# Orgel.net
KiCad netlist of a schematic drawn in EAGLE
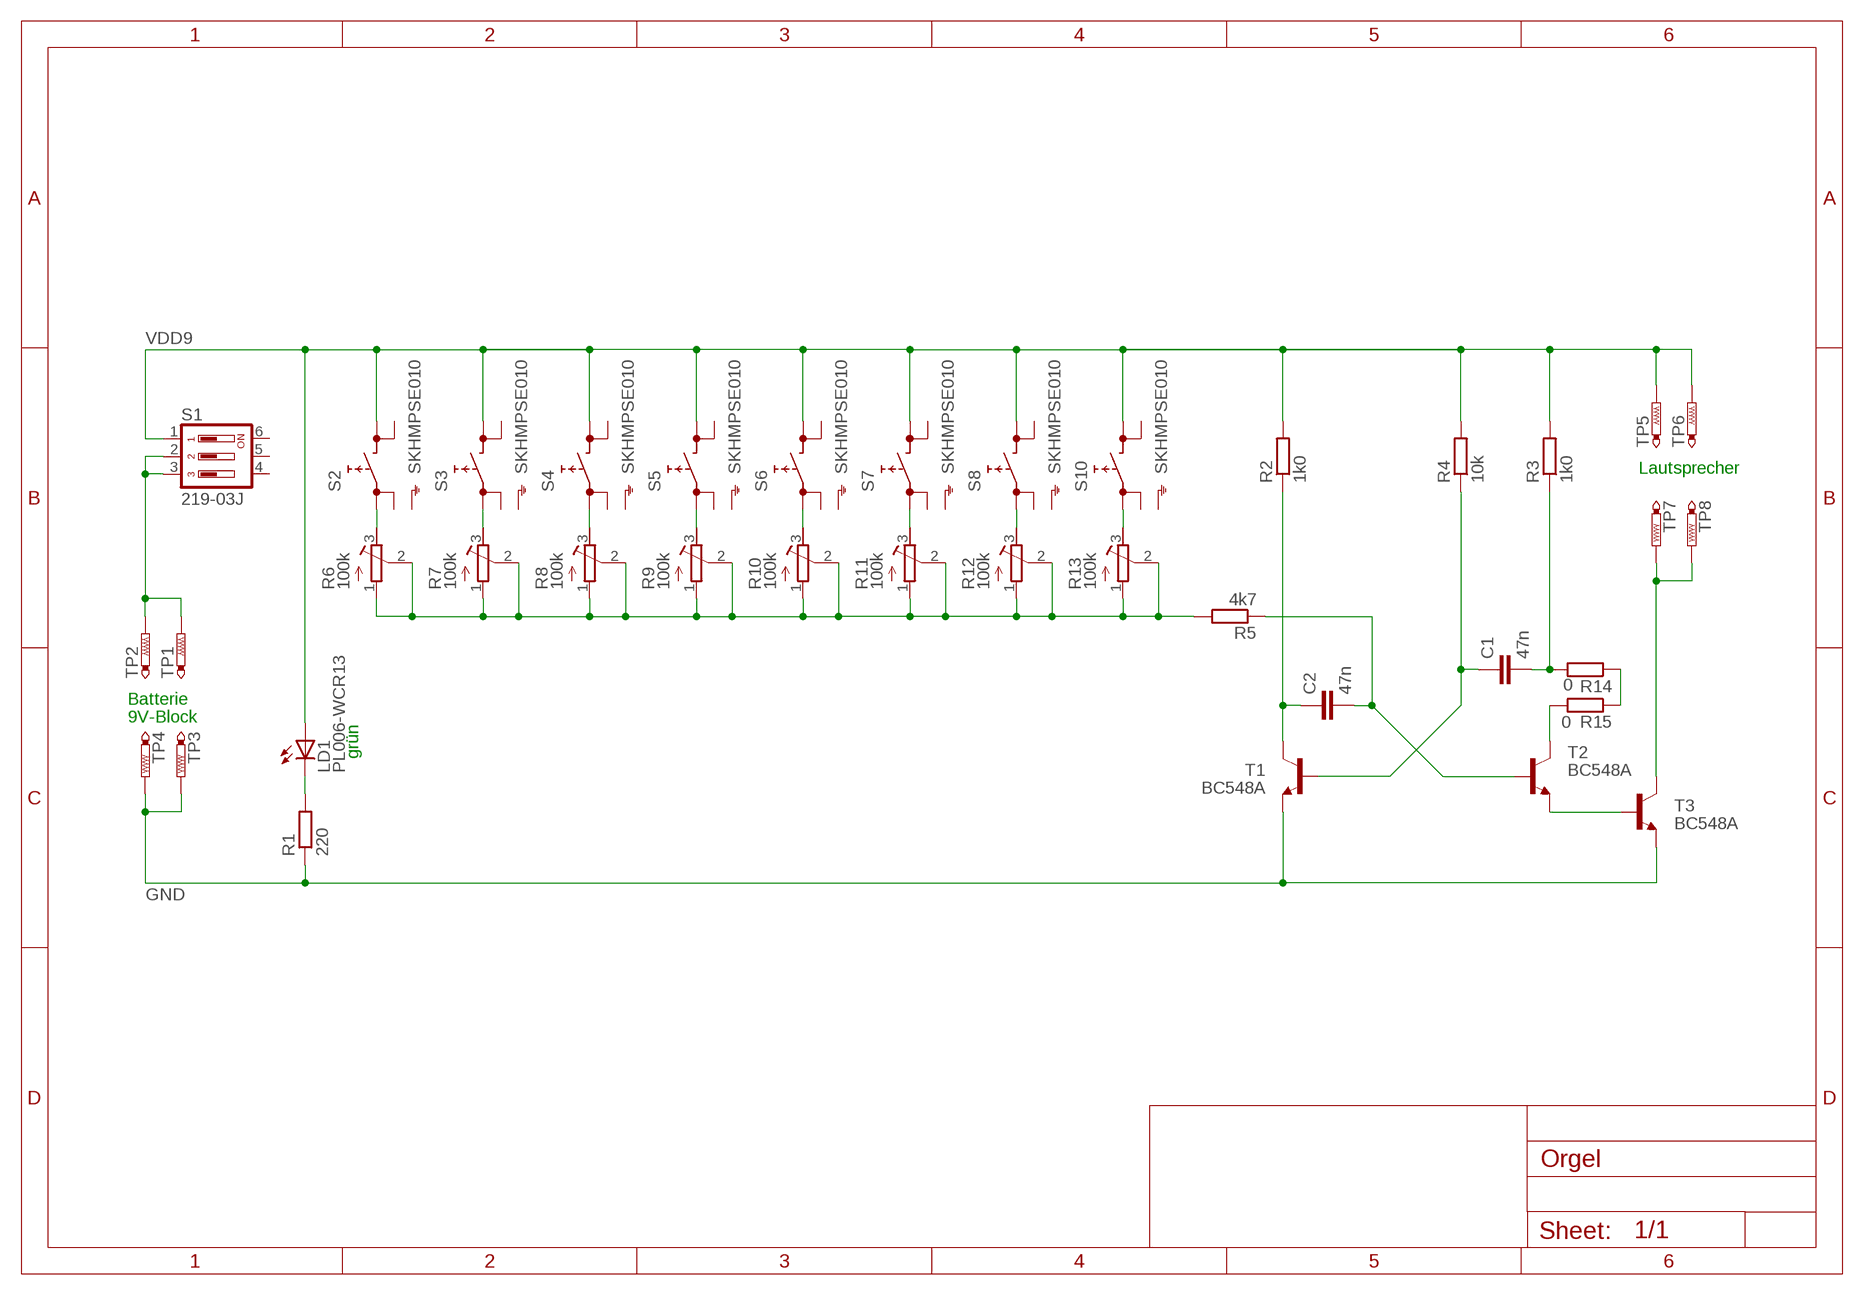
[diagram p0: schematic, sheet 1]

(export (version "E")
  (design (tool "Eeschema 10.0.6"))
  (components
    (comp (ref "C1")
      (value "47n")
      (footprint "eagle-import:C1206")
      (libsource (lib "eagle-import") (part "C-EUC1206"))
    )
    (comp (ref "C2")
      (value "47n")
      (footprint "eagle-import:C1206")
      (libsource (lib "eagle-import") (part "C-EUC1206"))
    )
    (comp (ref "LD1")
      (value "PL006-WCR13")
      (footprint "eagle-import:SOT23")
      (libsource (lib "eagle-import") (part "PL006-WCR13"))
    )
    (comp (ref "R1")
      (value "220")
      (footprint "eagle-import:M1206")
      (libsource (lib "eagle-import") (part "R-EU_M1206"))
    )
    (comp (ref "R2")
      (value "1k0")
      (footprint "eagle-import:M1206")
      (libsource (lib "eagle-import") (part "R-EU_M1206"))
    )
    (comp (ref "R3")
      (value "1k0")
      (footprint "eagle-import:M1206")
      (libsource (lib "eagle-import") (part "R-EU_M1206"))
    )
    (comp (ref "R4")
      (value "10k")
      (footprint "eagle-import:M1206")
      (libsource (lib "eagle-import") (part "R-EU_M1206"))
    )
    (comp (ref "R5")
      (value "4k7")
      (footprint "eagle-import:M1206")
      (libsource (lib "eagle-import") (part "R-EU_M1206"))
    )
    (comp (ref "R6")
      (value "100k")
      (footprint "eagle-import:RTRIM5X")
      (libsource (lib "eagle-import") (part "R-TRIMM5X"))
    )
    (comp (ref "R7")
      (value "100k")
      (footprint "eagle-import:RTRIM5X")
      (libsource (lib "eagle-import") (part "R-TRIMM5X"))
    )
    (comp (ref "R8")
      (value "100k")
      (footprint "eagle-import:RTRIM5X")
      (libsource (lib "eagle-import") (part "R-TRIMM5X"))
    )
    (comp (ref "R9")
      (value "100k")
      (footprint "eagle-import:RTRIM5X")
      (libsource (lib "eagle-import") (part "R-TRIMM5X"))
    )
    (comp (ref "R10")
      (value "100k")
      (footprint "eagle-import:RTRIM5X")
      (libsource (lib "eagle-import") (part "R-TRIMM5X"))
    )
    (comp (ref "R11")
      (value "100k")
      (footprint "eagle-import:RTRIM5X")
      (libsource (lib "eagle-import") (part "R-TRIMM5X"))
    )
    (comp (ref "R12")
      (value "100k")
      (footprint "eagle-import:RTRIM5X")
      (libsource (lib "eagle-import") (part "R-TRIMM5X"))
    )
    (comp (ref "R13")
      (value "100k")
      (footprint "eagle-import:RTRIM5X")
      (libsource (lib "eagle-import") (part "R-TRIMM5X"))
    )
    (comp (ref "R14")
      (value "0")
      (footprint "eagle-import:M5923")
      (libsource (lib "eagle-import") (part "R-EU_M5923"))
    )
    (comp (ref "R15")
      (value "0")
      (footprint "eagle-import:M5923")
      (libsource (lib "eagle-import") (part "R-EU_M5923"))
    )
    (comp (ref "S1")
      (value "219-03J")
      (footprint "eagle-import:CTS-219-03J")
      (libsource (lib "eagle-import") (part "219-03J"))
    )
    (comp (ref "S2")
      (value "SKHMPSE010")
      (footprint "eagle-import:SKHMPXE010")
      (libsource (lib "eagle-import") (part "SKHMPE010S"))
    )
    (comp (ref "S3")
      (value "SKHMPSE010")
      (footprint "eagle-import:SKHMPXE010")
      (libsource (lib "eagle-import") (part "SKHMPE010S"))
    )
    (comp (ref "S4")
      (value "SKHMPSE010")
      (footprint "eagle-import:SKHMPXE010")
      (libsource (lib "eagle-import") (part "SKHMPE010S"))
    )
    (comp (ref "S5")
      (value "SKHMPSE010")
      (footprint "eagle-import:SKHMPXE010")
      (libsource (lib "eagle-import") (part "SKHMPE010S"))
    )
    (comp (ref "S6")
      (value "SKHMPSE010")
      (footprint "eagle-import:SKHMPXE010")
      (libsource (lib "eagle-import") (part "SKHMPE010S"))
    )
    (comp (ref "S7")
      (value "SKHMPSE010")
      (footprint "eagle-import:SKHMPXE010")
      (libsource (lib "eagle-import") (part "SKHMPE010S"))
    )
    (comp (ref "S8")
      (value "SKHMPSE010")
      (footprint "eagle-import:SKHMPXE010")
      (libsource (lib "eagle-import") (part "SKHMPE010S"))
    )
    (comp (ref "S10")
      (value "SKHMPSE010")
      (footprint "eagle-import:SKHMPXE010")
      (libsource (lib "eagle-import") (part "SKHMPE010S"))
    )
    (comp (ref "T1")
      (value "BC548A")
      (footprint "eagle-import:SOT23-EBC")
      (libsource (lib "eagle-import") (part "-NPN-SOT23-EBC"))
    )
    (comp (ref "T2")
      (value "BC548A")
      (footprint "eagle-import:SOT23-EBC")
      (libsource (lib "eagle-import") (part "-NPN-SOT23-EBC"))
    )
    (comp (ref "T3")
      (value "BC548A")
      (footprint "eagle-import:SOT23-EBC")
      (libsource (lib "eagle-import") (part "-NPN-SOT23-EBC"))
    )
    (comp (ref "TP1")
      (value "PTR1TP20SQ")
      (footprint "eagle-import:TP20SQ")
      (libsource (lib "eagle-import") (part "PTR1TP20SQ"))
    )
    (comp (ref "TP2")
      (value "PTR1TP20SQ")
      (footprint "eagle-import:TP20SQ")
      (libsource (lib "eagle-import") (part "PTR1TP20SQ"))
    )
    (comp (ref "TP3")
      (value "PTR1TP20SQ")
      (footprint "eagle-import:TP20SQ")
      (libsource (lib "eagle-import") (part "PTR1TP20SQ"))
    )
    (comp (ref "TP4")
      (value "PTR1TP20SQ")
      (footprint "eagle-import:TP20SQ")
      (libsource (lib "eagle-import") (part "PTR1TP20SQ"))
    )
    (comp (ref "TP5")
      (value "PTR1TP20SQ")
      (footprint "eagle-import:TP20SQ")
      (libsource (lib "eagle-import") (part "PTR1TP20SQ"))
    )
    (comp (ref "TP6")
      (value "PTR1TP20SQ")
      (footprint "eagle-import:TP20SQ")
      (libsource (lib "eagle-import") (part "PTR1TP20SQ"))
    )
    (comp (ref "TP7")
      (value "PTR1TP20SQ")
      (footprint "eagle-import:TP20SQ")
      (libsource (lib "eagle-import") (part "PTR1TP20SQ"))
    )
    (comp (ref "TP8")
      (value "PTR1TP20SQ")
      (footprint "eagle-import:TP20SQ")
      (libsource (lib "eagle-import") (part "PTR1TP20SQ"))
    )
  )
  (nets
    (net (code "1") (name "/GND") (class "Default")
      (node (ref "R1") (pin "1") (pinfunction "1_1") (pintype "passive"))
      (node (ref "T1") (pin "E") (pinfunction "E_E") (pintype "passive"))
      (node (ref "T3") (pin "E") (pinfunction "E_E") (pintype "passive"))
      (node (ref "TP3") (pin "TP") (pinfunction "TP_TP") (pintype "input"))
      (node (ref "TP4") (pin "TP") (pinfunction "TP_TP") (pintype "input"))
    )
    (net (code "2") (name "/VDD9") (class "Default")
      (node (ref "LD1") (pin "1") (pinfunction "A_1") (pintype "passive"))
      (node (ref "R2") (pin "2") (pinfunction "2_2") (pintype "passive"))
      (node (ref "R3") (pin "2") (pinfunction "2_2") (pintype "passive"))
      (node (ref "R4") (pin "2") (pinfunction "2_2") (pintype "passive"))
      (node (ref "S1") (pin "1") (pinfunction "1_1") (pintype "passive"))
      (node (ref "S10") (pin "3") (pinfunction "2.1_3") (pintype "passive"))
      (node (ref "S2") (pin "3") (pinfunction "2.1_3") (pintype "passive"))
      (node (ref "S3") (pin "3") (pinfunction "2.1_3") (pintype "passive"))
      (node (ref "S4") (pin "3") (pinfunction "2.1_3") (pintype "passive"))
      (node (ref "S5") (pin "3") (pinfunction "2.1_3") (pintype "passive"))
      (node (ref "S6") (pin "3") (pinfunction "2.1_3") (pintype "passive"))
      (node (ref "S7") (pin "3") (pinfunction "2.1_3") (pintype "passive"))
      (node (ref "S8") (pin "3") (pinfunction "2.1_3") (pintype "passive"))
      (node (ref "TP5") (pin "TP") (pinfunction "TP_TP") (pintype "input"))
      (node (ref "TP6") (pin "TP") (pinfunction "TP_TP") (pintype "input"))
    )
    (net (code "3") (name "Net-(C1-Pad1)") (class "Default")
      (node (ref "C1") (pin "1") (pinfunction "1_1") (pintype "passive"))
      (node (ref "R4") (pin "1") (pinfunction "1_1") (pintype "passive"))
      (node (ref "T1") (pin "B") (pinfunction "B_B") (pintype "passive"))
    )
    (net (code "4") (name "Net-(C1-Pad2)") (class "Default")
      (node (ref "C1") (pin "2") (pinfunction "2_2") (pintype "passive"))
      (node (ref "R14") (pin "2") (pinfunction "2_2") (pintype "passive"))
      (node (ref "R3") (pin "1") (pinfunction "1_1") (pintype "passive"))
    )
    (net (code "5") (name "Net-(C2-Pad1)") (class "Default")
      (node (ref "C2") (pin "1") (pinfunction "1_1") (pintype "passive"))
      (node (ref "R2") (pin "1") (pinfunction "1_1") (pintype "passive"))
      (node (ref "T1") (pin "C") (pinfunction "C_C") (pintype "passive"))
    )
    (net (code "6") (name "Net-(C2-Pad2)") (class "Default")
      (node (ref "C2") (pin "2") (pinfunction "2_2") (pintype "passive"))
      (node (ref "R5") (pin "1") (pinfunction "1_1") (pintype "passive"))
      (node (ref "T2") (pin "B") (pinfunction "B_B") (pintype "passive"))
    )
    (net (code "7") (name "Net-(LD1-C)") (class "Default")
      (node (ref "LD1") (pin "3") (pinfunction "C_3") (pintype "passive"))
      (node (ref "R1") (pin "2") (pinfunction "2_2") (pintype "passive"))
    )
    (net (code "8") (name "Net-(R6-E)") (class "Default")
      (node (ref "R6") (pin "3") (pinfunction "E_3") (pintype "passive"))
      (node (ref "S2") (pin "1") (pinfunction "1.1_1") (pintype "passive"))
    )
    (net (code "9") (name "Net-(R7-E)") (class "Default")
      (node (ref "R7") (pin "3") (pinfunction "E_3") (pintype "passive"))
      (node (ref "S3") (pin "1") (pinfunction "1.1_1") (pintype "passive"))
    )
    (net (code "10") (name "Net-(R8-E)") (class "Default")
      (node (ref "R8") (pin "3") (pinfunction "E_3") (pintype "passive"))
      (node (ref "S4") (pin "1") (pinfunction "1.1_1") (pintype "passive"))
    )
    (net (code "11") (name "Net-(R9-E)") (class "Default")
      (node (ref "R9") (pin "3") (pinfunction "E_3") (pintype "passive"))
      (node (ref "S5") (pin "1") (pinfunction "1.1_1") (pintype "passive"))
    )
    (net (code "12") (name "Net-(R10-A)") (class "Default")
      (node (ref "R10") (pin "1") (pinfunction "A_1") (pintype "passive"))
      (node (ref "R10") (pin "2") (pinfunction "S_2") (pintype "passive"))
      (node (ref "R11") (pin "1") (pinfunction "A_1") (pintype "passive"))
      (node (ref "R11") (pin "2") (pinfunction "S_2") (pintype "passive"))
      (node (ref "R12") (pin "1") (pinfunction "A_1") (pintype "passive"))
      (node (ref "R12") (pin "2") (pinfunction "S_2") (pintype "passive"))
      (node (ref "R13") (pin "1") (pinfunction "A_1") (pintype "passive"))
      (node (ref "R13") (pin "2") (pinfunction "S_2") (pintype "passive"))
      (node (ref "R5") (pin "2") (pinfunction "2_2") (pintype "passive"))
      (node (ref "R6") (pin "1") (pinfunction "A_1") (pintype "passive"))
      (node (ref "R6") (pin "2") (pinfunction "S_2") (pintype "passive"))
      (node (ref "R7") (pin "1") (pinfunction "A_1") (pintype "passive"))
      (node (ref "R7") (pin "2") (pinfunction "S_2") (pintype "passive"))
      (node (ref "R8") (pin "1") (pinfunction "A_1") (pintype "passive"))
      (node (ref "R8") (pin "2") (pinfunction "S_2") (pintype "passive"))
      (node (ref "R9") (pin "1") (pinfunction "A_1") (pintype "passive"))
      (node (ref "R9") (pin "2") (pinfunction "S_2") (pintype "passive"))
    )
    (net (code "13") (name "Net-(R10-E)") (class "Default")
      (node (ref "R10") (pin "3") (pinfunction "E_3") (pintype "passive"))
      (node (ref "S6") (pin "1") (pinfunction "1.1_1") (pintype "passive"))
    )
    (net (code "14") (name "Net-(R11-E)") (class "Default")
      (node (ref "R11") (pin "3") (pinfunction "E_3") (pintype "passive"))
      (node (ref "S7") (pin "1") (pinfunction "1.1_1") (pintype "passive"))
    )
    (net (code "15") (name "Net-(R12-E)") (class "Default")
      (node (ref "R12") (pin "3") (pinfunction "E_3") (pintype "passive"))
      (node (ref "S8") (pin "1") (pinfunction "1.1_1") (pintype "passive"))
    )
    (net (code "16") (name "Net-(R13-E)") (class "Default")
      (node (ref "R13") (pin "3") (pinfunction "E_3") (pintype "passive"))
      (node (ref "S10") (pin "1") (pinfunction "1.1_1") (pintype "passive"))
    )
    (net (code "17") (name "Net-(R14-Pad1)") (class "Default")
      (node (ref "R14") (pin "1") (pinfunction "1_1") (pintype "passive"))
      (node (ref "R15") (pin "1") (pinfunction "1_1") (pintype "passive"))
    )
    (net (code "18") (name "Net-(R15-Pad2)") (class "Default")
      (node (ref "R15") (pin "2") (pinfunction "2_2") (pintype "passive"))
      (node (ref "T2") (pin "C") (pinfunction "C_C") (pintype "passive"))
    )
    (net (code "19") (name "Net-(S1-Pad2)") (class "Default")
      (node (ref "S1") (pin "2") (pinfunction "2_2") (pintype "passive"))
      (node (ref "S1") (pin "3") (pinfunction "3_3") (pintype "passive"))
      (node (ref "TP1") (pin "TP") (pinfunction "TP_TP") (pintype "input"))
      (node (ref "TP2") (pin "TP") (pinfunction "TP_TP") (pintype "input"))
    )
    (net (code "20") (name "Net-(T2-PadE)") (class "Default")
      (node (ref "T2") (pin "E") (pinfunction "E_E") (pintype "passive"))
      (node (ref "T3") (pin "B") (pinfunction "B_B") (pintype "passive"))
    )
    (net (code "21") (name "Net-(T3-PadC)") (class "Default")
      (node (ref "T3") (pin "C") (pinfunction "C_C") (pintype "passive"))
      (node (ref "TP7") (pin "TP") (pinfunction "TP_TP") (pintype "input"))
      (node (ref "TP8") (pin "TP") (pinfunction "TP_TP") (pintype "input"))
    )
    (net (code "22") (name "unconnected-(S1-Pad4)") (class "Default")
      (node (ref "S1") (pin "4") (pinfunction "4_4") (pintype "passive"))
    )
    (net (code "23") (name "unconnected-(S1-Pad5)") (class "Default")
      (node (ref "S1") (pin "5") (pinfunction "5_5") (pintype "passive"))
    )
    (net (code "24") (name "unconnected-(S1-Pad6)") (class "Default")
      (node (ref "S1") (pin "6") (pinfunction "6_6") (pintype "passive"))
    )
    (net (code "25") (name "unconnected-(S2-1.2-Pad2)") (class "Default")
      (node (ref "S2") (pin "2") (pinfunction "1.2_2") (pintype "passive"))
    )
    (net (code "26") (name "unconnected-(S2-2.2-Pad4)") (class "Default")
      (node (ref "S2") (pin "4") (pinfunction "2.2_4") (pintype "passive"))
    )
    (net (code "27") (name "unconnected-(S2-SH-Pad5)") (class "Default")
      (node (ref "S2") (pin "5") (pinfunction "SH_5") (pintype "passive"))
    )
    (net (code "28") (name "unconnected-(S3-1.2-Pad2)") (class "Default")
      (node (ref "S3") (pin "2") (pinfunction "1.2_2") (pintype "passive"))
    )
    (net (code "29") (name "unconnected-(S3-2.2-Pad4)") (class "Default")
      (node (ref "S3") (pin "4") (pinfunction "2.2_4") (pintype "passive"))
    )
    (net (code "30") (name "unconnected-(S3-SH-Pad5)") (class "Default")
      (node (ref "S3") (pin "5") (pinfunction "SH_5") (pintype "passive"))
    )
    (net (code "31") (name "unconnected-(S4-1.2-Pad2)") (class "Default")
      (node (ref "S4") (pin "2") (pinfunction "1.2_2") (pintype "passive"))
    )
    (net (code "32") (name "unconnected-(S4-2.2-Pad4)") (class "Default")
      (node (ref "S4") (pin "4") (pinfunction "2.2_4") (pintype "passive"))
    )
    (net (code "33") (name "unconnected-(S4-SH-Pad5)") (class "Default")
      (node (ref "S4") (pin "5") (pinfunction "SH_5") (pintype "passive"))
    )
    (net (code "34") (name "unconnected-(S5-1.2-Pad2)") (class "Default")
      (node (ref "S5") (pin "2") (pinfunction "1.2_2") (pintype "passive"))
    )
    (net (code "35") (name "unconnected-(S5-2.2-Pad4)") (class "Default")
      (node (ref "S5") (pin "4") (pinfunction "2.2_4") (pintype "passive"))
    )
    (net (code "36") (name "unconnected-(S5-SH-Pad5)") (class "Default")
      (node (ref "S5") (pin "5") (pinfunction "SH_5") (pintype "passive"))
    )
    (net (code "37") (name "unconnected-(S6-1.2-Pad2)") (class "Default")
      (node (ref "S6") (pin "2") (pinfunction "1.2_2") (pintype "passive"))
    )
    (net (code "38") (name "unconnected-(S6-2.2-Pad4)") (class "Default")
      (node (ref "S6") (pin "4") (pinfunction "2.2_4") (pintype "passive"))
    )
    (net (code "39") (name "unconnected-(S6-SH-Pad5)") (class "Default")
      (node (ref "S6") (pin "5") (pinfunction "SH_5") (pintype "passive"))
    )
    (net (code "40") (name "unconnected-(S7-1.2-Pad2)") (class "Default")
      (node (ref "S7") (pin "2") (pinfunction "1.2_2") (pintype "passive"))
    )
    (net (code "41") (name "unconnected-(S7-2.2-Pad4)") (class "Default")
      (node (ref "S7") (pin "4") (pinfunction "2.2_4") (pintype "passive"))
    )
    (net (code "42") (name "unconnected-(S7-SH-Pad5)") (class "Default")
      (node (ref "S7") (pin "5") (pinfunction "SH_5") (pintype "passive"))
    )
    (net (code "43") (name "unconnected-(S8-1.2-Pad2)") (class "Default")
      (node (ref "S8") (pin "2") (pinfunction "1.2_2") (pintype "passive"))
    )
    (net (code "44") (name "unconnected-(S8-2.2-Pad4)") (class "Default")
      (node (ref "S8") (pin "4") (pinfunction "2.2_4") (pintype "passive"))
    )
    (net (code "45") (name "unconnected-(S8-SH-Pad5)") (class "Default")
      (node (ref "S8") (pin "5") (pinfunction "SH_5") (pintype "passive"))
    )
    (net (code "46") (name "unconnected-(S10-1.2-Pad2)") (class "Default")
      (node (ref "S10") (pin "2") (pinfunction "1.2_2") (pintype "passive"))
    )
    (net (code "47") (name "unconnected-(S10-2.2-Pad4)") (class "Default")
      (node (ref "S10") (pin "4") (pinfunction "2.2_4") (pintype "passive"))
    )
    (net (code "48") (name "unconnected-(S10-SH-Pad5)") (class "Default")
      (node (ref "S10") (pin "5") (pinfunction "SH_5") (pintype "passive"))
    )
  )
)
